# SBC_65C02_ISA_IRQ_v2.net
KiCad netlist of a schematic drawn in EAGLE
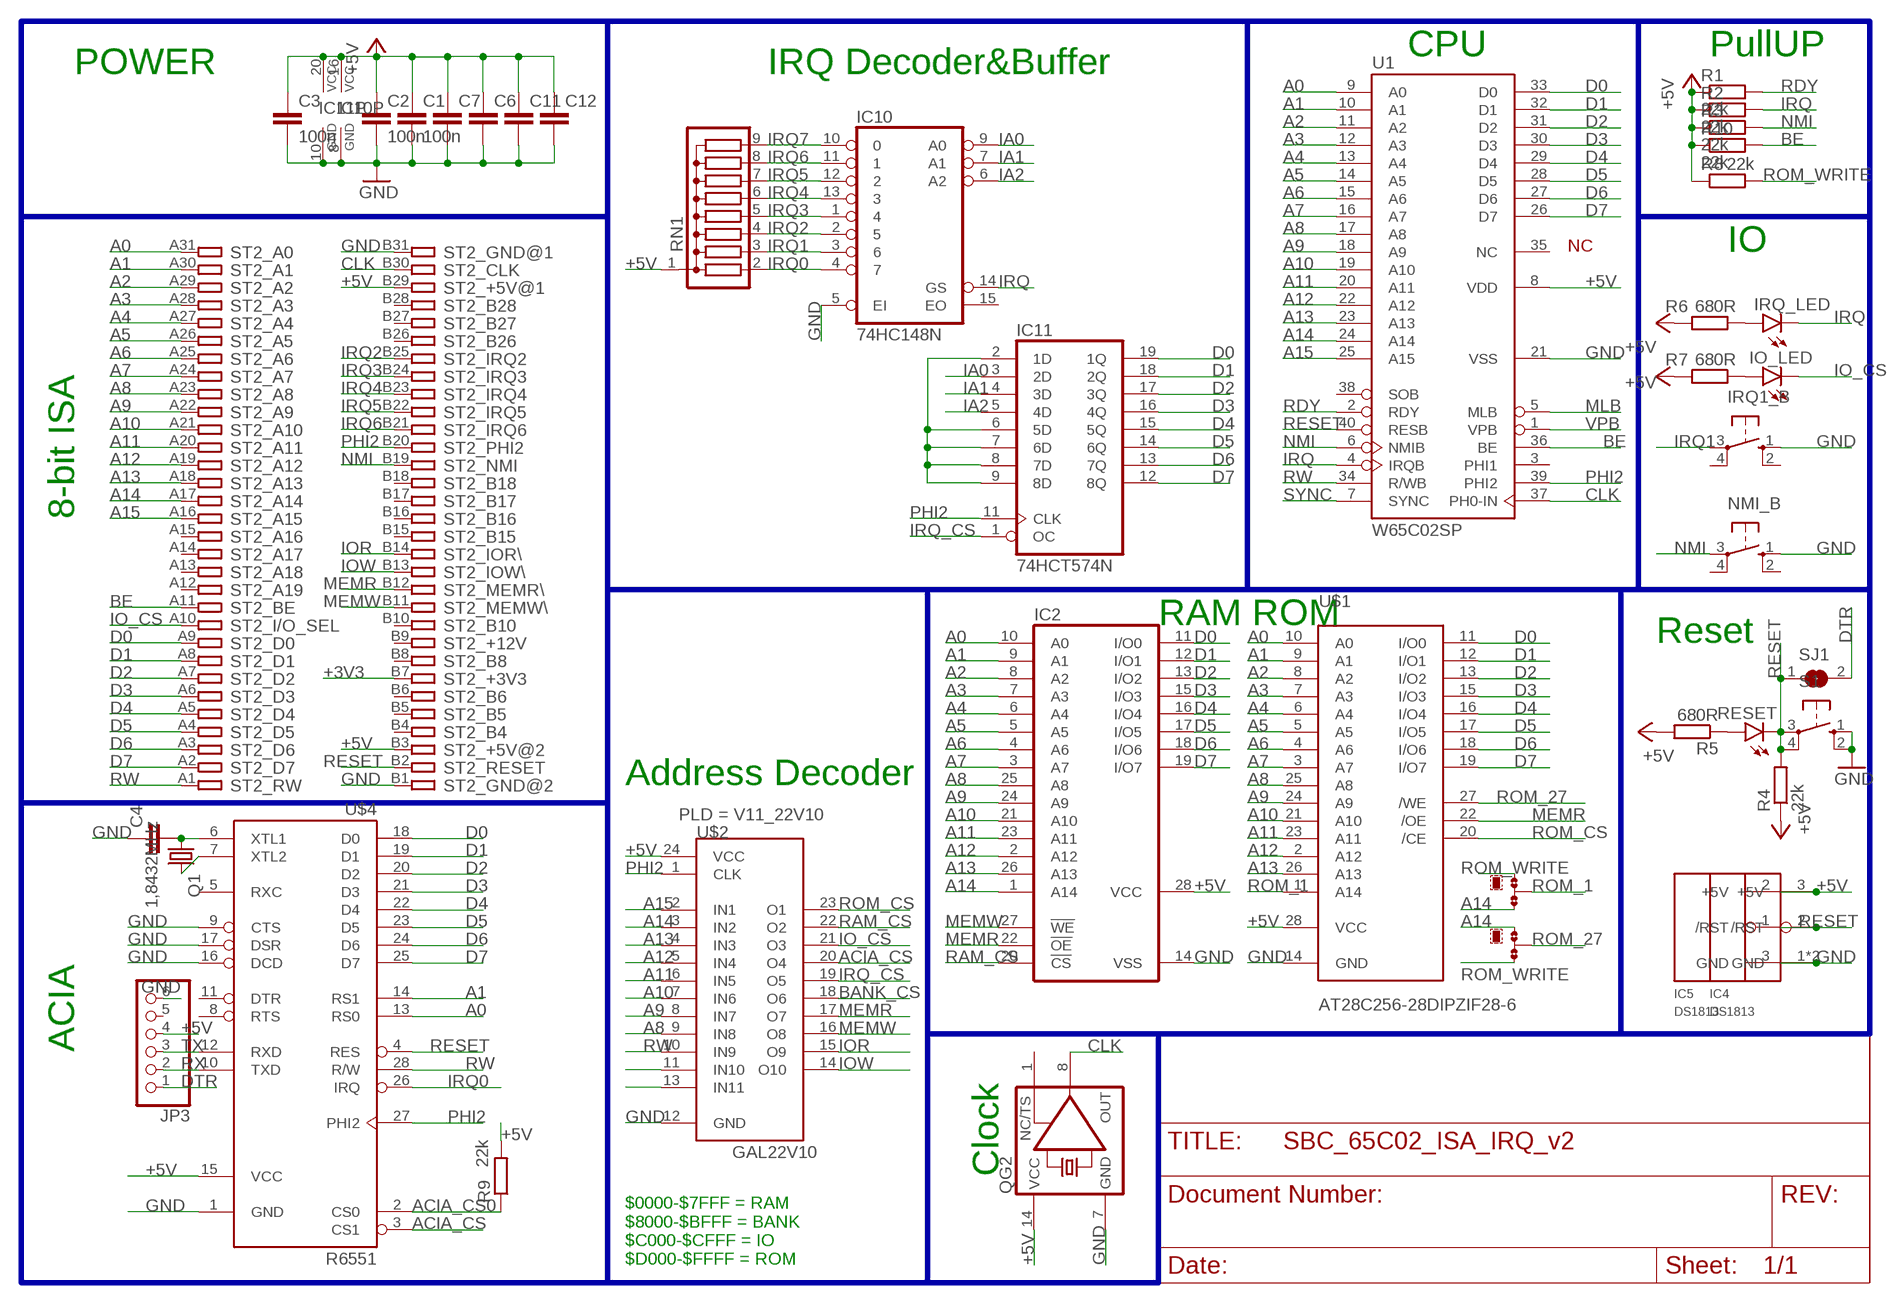
[diagram p0: schematic, sheet 1]

(export (version "E")
  (design (tool "Eeschema 10.0.6"))
  (components
    (comp (ref "C1")
      (value "100n")
      (footprint "eagle-import:C050-025X075")
      (libsource (lib "eagle-import") (part "C-EU050-025X075"))
    )
    (comp (ref "C2")
      (value "100n")
      (footprint "eagle-import:C050-025X075")
      (libsource (lib "eagle-import") (part "C-EU050-025X075"))
    )
    (comp (ref "C3")
      (value "100n")
      (footprint "eagle-import:C050-025X075")
      (libsource (lib "eagle-import") (part "C-EU050-025X075"))
    )
    (comp (ref "C4")
      (value "C-EU025-030X050")
      (footprint "eagle-import:C025-030X050")
      (libsource (lib "eagle-import") (part "rcl_334_C-EU025-030X050"))
    )
    (comp (ref "C6")
      (value "C-EU050-035X075")
      (footprint "eagle-import:C050-035X075")
      (libsource (lib "eagle-import") (part "rcl_334_C-EU050-035X075"))
    )
    (comp (ref "C7")
      (value "C-EU050-035X075")
      (footprint "eagle-import:C050-035X075")
      (libsource (lib "eagle-import") (part "rcl_334_C-EU050-035X075"))
    )
    (comp (ref "C11")
      (value "C-EU050-035X075")
      (footprint "eagle-import:C050-035X075")
      (libsource (lib "eagle-import") (part "rcl_334_C-EU050-035X075"))
    )
    (comp (ref "C12")
      (value "C-EU050-035X075")
      (footprint "eagle-import:C050-035X075")
      (libsource (lib "eagle-import") (part "rcl_334_C-EU050-035X075"))
    )
    (comp (ref "IC2")
      (value "62256P")
      (footprint "eagle-import:DIL28-6")
      (libsource (lib "eagle-import") (part "62256P"))
    )
    (comp (ref "IC4")
      (value "DS1813")
      (footprint "eagle-import:SOT223")
      (libsource (lib "eagle-import") (part "DS1813SOT-223"))
    )
    (comp (ref "IC5")
      (value "DS1813")
      (footprint "eagle-import:TO-92")
      (libsource (lib "eagle-import") (part "DS1813"))
    )
    (comp (ref "IC10")
      (value "74HC148N")
      (footprint "eagle-import:DIL16")
      (libsource (lib "eagle-import") (part "74148NHC"))
    )
    (comp (ref "IC11")
      (value "74HCT574N")
      (footprint "eagle-import:DIL20")
      (libsource (lib "eagle-import") (part "74574NHCT"))
    )
    (comp (ref "IO_LED")
      (value "LED5MM")
      (footprint "eagle-import:LED5MM")
      (libsource (lib "eagle-import") (part "LED5MM"))
    )
    (comp (ref "IRQ1_B")
      (value "10-XX")
      (footprint "eagle-import:B3F-10XX")
      (fields (field (name "MPN") "B3F-1000"))
      (libsource (lib "eagle-import") (part "10-XX"))
    )
    (comp (ref "IRQ_LED")
      (value "LED5MM")
      (footprint "eagle-import:LED5MM")
      (libsource (lib "eagle-import") (part "LED5MM"))
    )
    (comp (ref "JP3")
      (value "PINHD-1X6/90")
      (footprint "eagle-import:1X06_90")
      (libsource (lib "eagle-import") (part "PINHD-1X6/90"))
    )
    (comp (ref "NMI_B")
      (value "10-XX")
      (footprint "eagle-import:B3F-10XX")
      (fields (field (name "MPN") "B3F-1000"))
      (libsource (lib "eagle-import") (part "10-XX"))
    )
    (comp (ref "Q1")
      (value "1,8432MHz")
      (footprint "eagle-import:HC49_S")
      (libsource (lib "eagle-import") (part "CRYSTALHC49S"))
    )
    (comp (ref "QG2")
      (value "XO-14")
      (footprint "eagle-import:DIL14S")
      (libsource (lib "eagle-import") (part "XO-14"))
    )
    (comp (ref "R1")
      (value "22k")
      (footprint "eagle-import:0207_10")
      (libsource (lib "eagle-import") (part "R-EU_0207/10"))
    )
    (comp (ref "R2")
      (value "22k")
      (footprint "eagle-import:0207_10")
      (libsource (lib "eagle-import") (part "R-EU_0207/10"))
    )
    (comp (ref "R3")
      (value "22k")
      (footprint "eagle-import:0207_10")
      (libsource (lib "eagle-import") (part "R-EU_0207/10"))
    )
    (comp (ref "R4")
      (value "22k")
      (footprint "eagle-import:0207_10")
      (libsource (lib "eagle-import") (part "resistor_348_R-EU_0207/10"))
    )
    (comp (ref "R5")
      (value "680R")
      (footprint "eagle-import:0207_10")
      (libsource (lib "eagle-import") (part "resistor_348_R-EU_0207/10"))
    )
    (comp (ref "R6")
      (value "680R")
      (footprint "eagle-import:0207_10")
      (libsource (lib "eagle-import") (part "resistor_348_R-EU_0207/10"))
    )
    (comp (ref "R7")
      (value "680R")
      (footprint "eagle-import:0207_10")
      (libsource (lib "eagle-import") (part "resistor_348_R-EU_0207/10"))
    )
    (comp (ref "R8")
      (value "22k")
      (footprint "eagle-import:0207_10")
      (libsource (lib "eagle-import") (part "rcl_334_R-EU_0207/10"))
    )
    (comp (ref "R9")
      (value "22k")
      (footprint "eagle-import:0207_10")
      (libsource (lib "eagle-import") (part "rcl_334_R-EU_0207/10"))
    )
    (comp (ref "R10")
      (value "22k")
      (footprint "eagle-import:0207_10")
      (libsource (lib "eagle-import") (part "R-EU_0207/10"))
    )
    (comp (ref "RESET")
      (value "LED5MM")
      (footprint "eagle-import:LED5MM")
      (libsource (lib "eagle-import") (part "LED5MM"))
    )
    (comp (ref "RN1")
      (value "G08R")
      (footprint "eagle-import:SIL9")
      (libsource (lib "eagle-import") (part "G08R"))
    )
    (comp (ref "ROM_1")
      (value "0R-JUMPA")
      (footprint "eagle-import:A0R-JMP")
      (libsource (lib "eagle-import") (part "0R-JUMPA"))
    )
    (comp (ref "ROM_27")
      (value "0R-JUMPA")
      (footprint "eagle-import:A0R-JMP")
      (libsource (lib "eagle-import") (part "0R-JUMPA"))
    )
    (comp (ref "S1")
      (value "10-XX")
      (footprint "eagle-import:B3F-10XX")
      (fields (field (name "MPN") "B3F-1000"))
      (libsource (lib "eagle-import") (part "10-XX"))
    )
    (comp (ref "SJ1") (value "SJ") (footprint "eagle-import:SJ") (libsource (lib "eagle-import") (part "SJ")))
    (comp (ref "ST2")
      (value "IBM8BIT_ISA")
      (footprint "eagle-import:IBM8BIT")
      (libsource (lib "eagle-import") (part "IBM8BIT_ISA"))
    )
    (comp (ref "U$1")
      (value "AT28C256-28DIPZIF28-6")
      (footprint "eagle-import:228-1277-00-0602J")
      (libsource (lib "eagle-import") (part "AT28C256-28DIPZIF28-6"))
    )
    (comp (ref "U$2")
      (value "GAL22V10")
      (footprint "eagle-import:DIL28_1")
      (libsource (lib "eagle-import") (part "GAL22V10"))
    )
    (comp (ref "U$4")
      (value "R6551")
      (footprint "eagle-import:DIP-28")
      (libsource (lib "eagle-import") (part "R6551"))
    )
    (comp (ref "U1")
      (value "W65C02SP")
      (footprint "eagle-import:DIP-40")
      (libsource (lib "eagle-import") (part "W65C02SP"))
    )
  )
  (nets
    (net (code "1") (name "+5V") (class "Default")
      (node (ref "C1") (pin "1") (pinfunction "1_1") (pintype "passive"))
      (node (ref "C11") (pin "1") (pinfunction "1_1") (pintype "passive"))
      (node (ref "C12") (pin "1") (pinfunction "1_1") (pintype "passive"))
      (node (ref "C2") (pin "1") (pinfunction "1_1") (pintype "passive"))
      (node (ref "C3") (pin "1") (pinfunction "1_1") (pintype "passive"))
      (node (ref "C6") (pin "1") (pinfunction "1_1") (pintype "passive"))
      (node (ref "C7") (pin "1") (pinfunction "1_1") (pintype "passive"))
      (node (ref "IC10") (pin "16") (pinfunction "VCC_16") (pintype "power_in"))
      (node (ref "IC11") (pin "20") (pinfunction "VCC_20") (pintype "power_in"))
      (node (ref "IC2") (pin "28") (pinfunction "VCC_28") (pintype "power_in"))
      (node (ref "IC4") (pin "3") (pinfunction "+5V_3") (pintype "power_in"))
      (node (ref "IC5") (pin "2") (pinfunction "+5V_2") (pintype "power_in"))
      (node (ref "JP3") (pin "4") (pinfunction "4_4") (pintype "passive"))
      (node (ref "QG2") (pin "14") (pinfunction "VCC_14") (pintype "power_in"))
      (node (ref "R1") (pin "1") (pinfunction "1_1") (pintype "passive"))
      (node (ref "R10") (pin "1") (pinfunction "1_1") (pintype "passive"))
      (node (ref "R2") (pin "1") (pinfunction "1_1") (pintype "passive"))
      (node (ref "R3") (pin "1") (pinfunction "1_1") (pintype "passive"))
      (node (ref "R4") (pin "1") (pinfunction "1_1") (pintype "passive"))
      (node (ref "R5") (pin "2") (pinfunction "2_2") (pintype "passive"))
      (node (ref "R6") (pin "2") (pinfunction "2_2") (pintype "passive"))
      (node (ref "R7") (pin "2") (pinfunction "2_2") (pintype "passive"))
      (node (ref "R8") (pin "1") (pinfunction "1_1") (pintype "passive"))
      (node (ref "R9") (pin "2") (pinfunction "2_2") (pintype "passive"))
      (node (ref "RN1") (pin "1") (pinfunction "1_1") (pintype "passive"))
      (node (ref "ST2") (pin "B29") (pinfunction "P_B29") (pintype "bidirectional"))
      (node (ref "ST2") (pin "B3") (pinfunction "P_B3") (pintype "bidirectional"))
      (node (ref "U$1") (pin "28") (pinfunction "VCC_28") (pintype "bidirectional"))
      (node (ref "U$2") (pin "24") (pinfunction "VCC_24") (pintype "bidirectional"))
      (node (ref "U$4") (pin "15") (pinfunction "VCC_15") (pintype "power_in"))
      (node (ref "U1") (pin "8") (pinfunction "VDD_8") (pintype "power_in"))
    )
    (net (code "2") (name "/+3V3") (class "Default")
      (node (ref "ST2") (pin "B7") (pinfunction "P_B7") (pintype "bidirectional"))
    )
    (net (code "3") (name "/A0") (class "Default")
      (node (ref "IC2") (pin "10") (pinfunction "A0_10") (pintype "input"))
      (node (ref "ST2") (pin "A31") (pinfunction "P_A31") (pintype "bidirectional"))
      (node (ref "U$1") (pin "10") (pinfunction "A0_10") (pintype "bidirectional"))
      (node (ref "U$4") (pin "13") (pinfunction "RS0_13") (pintype "input"))
      (node (ref "U1") (pin "9") (pinfunction "A0_9") (pintype "bidirectional"))
    )
    (net (code "4") (name "/A1") (class "Default")
      (node (ref "IC2") (pin "9") (pinfunction "A1_9") (pintype "input"))
      (node (ref "ST2") (pin "A30") (pinfunction "P_A30") (pintype "bidirectional"))
      (node (ref "U$1") (pin "9") (pinfunction "A1_9") (pintype "bidirectional"))
      (node (ref "U$4") (pin "14") (pinfunction "RS1_14") (pintype "input"))
      (node (ref "U1") (pin "10") (pinfunction "A1_10") (pintype "bidirectional"))
    )
    (net (code "5") (name "/A2") (class "Default")
      (node (ref "IC2") (pin "8") (pinfunction "A2_8") (pintype "input"))
      (node (ref "ST2") (pin "A29") (pinfunction "P_A29") (pintype "bidirectional"))
      (node (ref "U$1") (pin "8") (pinfunction "A2_8") (pintype "bidirectional"))
      (node (ref "U1") (pin "11") (pinfunction "A2_11") (pintype "bidirectional"))
    )
    (net (code "6") (name "/A3") (class "Default")
      (node (ref "IC2") (pin "7") (pinfunction "A3_7") (pintype "input"))
      (node (ref "ST2") (pin "A28") (pinfunction "P_A28") (pintype "bidirectional"))
      (node (ref "U$1") (pin "7") (pinfunction "A3_7") (pintype "bidirectional"))
      (node (ref "U1") (pin "12") (pinfunction "A3_12") (pintype "bidirectional"))
    )
    (net (code "7") (name "/A4") (class "Default")
      (node (ref "IC2") (pin "6") (pinfunction "A4_6") (pintype "input"))
      (node (ref "ST2") (pin "A27") (pinfunction "P_A27") (pintype "bidirectional"))
      (node (ref "U$1") (pin "6") (pinfunction "A4_6") (pintype "bidirectional"))
      (node (ref "U1") (pin "13") (pinfunction "A4_13") (pintype "bidirectional"))
    )
    (net (code "8") (name "/A5") (class "Default")
      (node (ref "IC2") (pin "5") (pinfunction "A5_5") (pintype "input"))
      (node (ref "ST2") (pin "A26") (pinfunction "P_A26") (pintype "bidirectional"))
      (node (ref "U$1") (pin "5") (pinfunction "A5_5") (pintype "bidirectional"))
      (node (ref "U1") (pin "14") (pinfunction "A5_14") (pintype "bidirectional"))
    )
    (net (code "9") (name "/A6") (class "Default")
      (node (ref "IC2") (pin "4") (pinfunction "A6_4") (pintype "input"))
      (node (ref "ST2") (pin "A25") (pinfunction "P_A25") (pintype "bidirectional"))
      (node (ref "U$1") (pin "4") (pinfunction "A6_4") (pintype "bidirectional"))
      (node (ref "U1") (pin "15") (pinfunction "A6_15") (pintype "bidirectional"))
    )
    (net (code "10") (name "/A7") (class "Default")
      (node (ref "IC2") (pin "3") (pinfunction "A7_3") (pintype "input"))
      (node (ref "ST2") (pin "A24") (pinfunction "P_A24") (pintype "bidirectional"))
      (node (ref "U$1") (pin "3") (pinfunction "A7_3") (pintype "bidirectional"))
      (node (ref "U1") (pin "16") (pinfunction "A7_16") (pintype "bidirectional"))
    )
    (net (code "11") (name "/A8") (class "Default")
      (node (ref "IC2") (pin "25") (pinfunction "A8_25") (pintype "input"))
      (node (ref "ST2") (pin "A23") (pinfunction "P_A23") (pintype "bidirectional"))
      (node (ref "U$1") (pin "25") (pinfunction "A8_25") (pintype "bidirectional"))
      (node (ref "U$2") (pin "9") (pinfunction "IN8_9") (pintype "bidirectional"))
      (node (ref "U1") (pin "17") (pinfunction "A8_17") (pintype "bidirectional"))
    )
    (net (code "12") (name "/A9") (class "Default")
      (node (ref "IC2") (pin "24") (pinfunction "A9_24") (pintype "input"))
      (node (ref "ST2") (pin "A22") (pinfunction "P_A22") (pintype "bidirectional"))
      (node (ref "U$1") (pin "24") (pinfunction "A9_24") (pintype "bidirectional"))
      (node (ref "U$2") (pin "8") (pinfunction "IN7_8") (pintype "bidirectional"))
      (node (ref "U1") (pin "18") (pinfunction "A9_18") (pintype "bidirectional"))
    )
    (net (code "13") (name "/A10") (class "Default")
      (node (ref "IC2") (pin "21") (pinfunction "A10_21") (pintype "input"))
      (node (ref "ST2") (pin "A21") (pinfunction "P_A21") (pintype "bidirectional"))
      (node (ref "U$1") (pin "21") (pinfunction "A10_21") (pintype "bidirectional"))
      (node (ref "U$2") (pin "7") (pinfunction "IN6_7") (pintype "bidirectional"))
      (node (ref "U1") (pin "19") (pinfunction "A10_19") (pintype "bidirectional"))
    )
    (net (code "14") (name "/A11") (class "Default")
      (node (ref "IC2") (pin "23") (pinfunction "A11_23") (pintype "input"))
      (node (ref "ST2") (pin "A20") (pinfunction "P_A20") (pintype "bidirectional"))
      (node (ref "U$1") (pin "23") (pinfunction "A11_23") (pintype "bidirectional"))
      (node (ref "U$2") (pin "6") (pinfunction "IN5_6") (pintype "bidirectional"))
      (node (ref "U1") (pin "20") (pinfunction "A11_20") (pintype "bidirectional"))
    )
    (net (code "15") (name "/A12") (class "Default")
      (node (ref "IC2") (pin "2") (pinfunction "A12_2") (pintype "input"))
      (node (ref "ST2") (pin "A19") (pinfunction "P_A19") (pintype "bidirectional"))
      (node (ref "U$1") (pin "2") (pinfunction "A12_2") (pintype "bidirectional"))
      (node (ref "U$2") (pin "5") (pinfunction "IN4_5") (pintype "bidirectional"))
      (node (ref "U1") (pin "22") (pinfunction "A12_22") (pintype "bidirectional"))
    )
    (net (code "16") (name "/A13") (class "Default")
      (node (ref "IC2") (pin "26") (pinfunction "A13_26") (pintype "input"))
      (node (ref "ST2") (pin "A18") (pinfunction "P_A18") (pintype "bidirectional"))
      (node (ref "U$1") (pin "26") (pinfunction "A13_26") (pintype "bidirectional"))
      (node (ref "U$2") (pin "4") (pinfunction "IN3_4") (pintype "bidirectional"))
      (node (ref "U1") (pin "23") (pinfunction "A13_23") (pintype "bidirectional"))
    )
    (net (code "17") (name "/A14") (class "Default")
      (node (ref "IC2") (pin "1") (pinfunction "A14_1") (pintype "input"))
      (node (ref "ROM_1") (pin "3") (pinfunction "3_3") (pintype "passive"))
      (node (ref "ROM_27") (pin "1") (pinfunction "1_1") (pintype "passive"))
      (node (ref "ST2") (pin "A17") (pinfunction "P_A17") (pintype "bidirectional"))
      (node (ref "U$2") (pin "3") (pinfunction "IN2_3") (pintype "bidirectional"))
      (node (ref "U1") (pin "24") (pinfunction "A14_24") (pintype "bidirectional"))
    )
    (net (code "18") (name "/A15") (class "Default")
      (node (ref "ST2") (pin "A16") (pinfunction "P_A16") (pintype "bidirectional"))
      (node (ref "U$2") (pin "2") (pinfunction "IN1_2") (pintype "bidirectional"))
      (node (ref "U1") (pin "25") (pinfunction "A15_25") (pintype "bidirectional"))
    )
    (net (code "19") (name "/ACIA_CS") (class "Default")
      (node (ref "U$2") (pin "20") (pinfunction "O4_20") (pintype "bidirectional"))
      (node (ref "U$4") (pin "3") (pinfunction "CS1_3") (pintype "input"))
    )
    (net (code "20") (name "/ACIA_CS0") (class "Default")
      (node (ref "R9") (pin "1") (pinfunction "1_1") (pintype "passive"))
      (node (ref "U$4") (pin "2") (pinfunction "CS0_2") (pintype "input"))
    )
    (net (code "21") (name "/BANK_CS") (class "Default")
      (node (ref "U$2") (pin "18") (pinfunction "O6_18") (pintype "bidirectional"))
    )
    (net (code "22") (name "/BE") (class "Default")
      (node (ref "R10") (pin "2") (pinfunction "2_2") (pintype "passive"))
      (node (ref "ST2") (pin "A11") (pinfunction "P_A11") (pintype "bidirectional"))
      (node (ref "U1") (pin "36") (pinfunction "BE_36") (pintype "input"))
    )
    (net (code "23") (name "/CLK") (class "Default")
      (node (ref "QG2") (pin "8") (pinfunction "OUT_8") (pintype "output"))
      (node (ref "ST2") (pin "B30") (pinfunction "P_B30") (pintype "bidirectional"))
      (node (ref "U1") (pin "37") (pinfunction "PH0-IN_37") (pintype "input"))
    )
    (net (code "24") (name "/D0") (class "Default")
      (node (ref "IC11") (pin "19") (pinfunction "1Q_19") (pintype "tri_state"))
      (node (ref "IC2") (pin "11") (pinfunction "I/O0_11") (pintype "bidirectional"))
      (node (ref "ST2") (pin "A9") (pinfunction "P_A9") (pintype "bidirectional"))
      (node (ref "U$1") (pin "11") (pinfunction "I/O0_11") (pintype "bidirectional"))
      (node (ref "U$4") (pin "18") (pinfunction "D0_18") (pintype "bidirectional"))
      (node (ref "U1") (pin "33") (pinfunction "D0_33") (pintype "bidirectional"))
    )
    (net (code "25") (name "/D1") (class "Default")
      (node (ref "IC11") (pin "18") (pinfunction "2Q_18") (pintype "tri_state"))
      (node (ref "IC2") (pin "12") (pinfunction "I/O1_12") (pintype "bidirectional"))
      (node (ref "ST2") (pin "A8") (pinfunction "P_A8") (pintype "bidirectional"))
      (node (ref "U$1") (pin "12") (pinfunction "I/O1_12") (pintype "bidirectional"))
      (node (ref "U$4") (pin "19") (pinfunction "D1_19") (pintype "bidirectional"))
      (node (ref "U1") (pin "32") (pinfunction "D1_32") (pintype "bidirectional"))
    )
    (net (code "26") (name "/D2") (class "Default")
      (node (ref "IC11") (pin "17") (pinfunction "3Q_17") (pintype "tri_state"))
      (node (ref "IC2") (pin "13") (pinfunction "I/O2_13") (pintype "bidirectional"))
      (node (ref "ST2") (pin "A7") (pinfunction "P_A7") (pintype "bidirectional"))
      (node (ref "U$1") (pin "13") (pinfunction "I/O2_13") (pintype "bidirectional"))
      (node (ref "U$4") (pin "20") (pinfunction "D2_20") (pintype "bidirectional"))
      (node (ref "U1") (pin "31") (pinfunction "D2_31") (pintype "bidirectional"))
    )
    (net (code "27") (name "/D3") (class "Default")
      (node (ref "IC11") (pin "16") (pinfunction "4Q_16") (pintype "tri_state"))
      (node (ref "IC2") (pin "15") (pinfunction "I/O3_15") (pintype "bidirectional"))
      (node (ref "ST2") (pin "A6") (pinfunction "P_A6") (pintype "bidirectional"))
      (node (ref "U$1") (pin "15") (pinfunction "I/O3_15") (pintype "bidirectional"))
      (node (ref "U$4") (pin "21") (pinfunction "D3_21") (pintype "bidirectional"))
      (node (ref "U1") (pin "30") (pinfunction "D3_30") (pintype "bidirectional"))
    )
    (net (code "28") (name "/D4") (class "Default")
      (node (ref "IC11") (pin "15") (pinfunction "5Q_15") (pintype "tri_state"))
      (node (ref "IC2") (pin "16") (pinfunction "I/O4_16") (pintype "bidirectional"))
      (node (ref "ST2") (pin "A5") (pinfunction "P_A5") (pintype "bidirectional"))
      (node (ref "U$1") (pin "16") (pinfunction "I/O4_16") (pintype "bidirectional"))
      (node (ref "U$4") (pin "22") (pinfunction "D4_22") (pintype "bidirectional"))
      (node (ref "U1") (pin "29") (pinfunction "D4_29") (pintype "bidirectional"))
    )
    (net (code "29") (name "/D5") (class "Default")
      (node (ref "IC11") (pin "14") (pinfunction "6Q_14") (pintype "tri_state"))
      (node (ref "IC2") (pin "17") (pinfunction "I/O5_17") (pintype "bidirectional"))
      (node (ref "ST2") (pin "A4") (pinfunction "P_A4") (pintype "bidirectional"))
      (node (ref "U$1") (pin "17") (pinfunction "I/O5_17") (pintype "bidirectional"))
      (node (ref "U$4") (pin "23") (pinfunction "D5_23") (pintype "bidirectional"))
      (node (ref "U1") (pin "28") (pinfunction "D5_28") (pintype "bidirectional"))
    )
    (net (code "30") (name "/D6") (class "Default")
      (node (ref "IC11") (pin "13") (pinfunction "7Q_13") (pintype "tri_state"))
      (node (ref "IC2") (pin "18") (pinfunction "I/O6_18") (pintype "bidirectional"))
      (node (ref "ST2") (pin "A3") (pinfunction "P_A3") (pintype "bidirectional"))
      (node (ref "U$1") (pin "18") (pinfunction "I/O6_18") (pintype "bidirectional"))
      (node (ref "U$4") (pin "24") (pinfunction "D6_24") (pintype "bidirectional"))
      (node (ref "U1") (pin "27") (pinfunction "D6_27") (pintype "bidirectional"))
    )
    (net (code "31") (name "/D7") (class "Default")
      (node (ref "IC11") (pin "12") (pinfunction "8Q_12") (pintype "tri_state"))
      (node (ref "IC2") (pin "19") (pinfunction "I/O7_19") (pintype "bidirectional"))
      (node (ref "ST2") (pin "A2") (pinfunction "P_A2") (pintype "bidirectional"))
      (node (ref "U$1") (pin "19") (pinfunction "I/O7_19") (pintype "bidirectional"))
      (node (ref "U$4") (pin "25") (pinfunction "D7_25") (pintype "bidirectional"))
      (node (ref "U1") (pin "26") (pinfunction "D7_26") (pintype "bidirectional"))
    )
    (net (code "32") (name "/DTR") (class "Default")
      (node (ref "JP3") (pin "1") (pinfunction "1_1") (pintype "passive"))
      (node (ref "SJ1") (pin "2") (pinfunction "2_2") (pintype "passive"))
    )
    (net (code "33") (name "/IA0") (class "Default")
      (node (ref "IC10") (pin "9") (pinfunction "A0_9") (pintype "output"))
      (node (ref "IC11") (pin "3") (pinfunction "2D_3") (pintype "input"))
    )
    (net (code "34") (name "/IA1") (class "Default")
      (node (ref "IC10") (pin "7") (pinfunction "A1_7") (pintype "output"))
      (node (ref "IC11") (pin "4") (pinfunction "3D_4") (pintype "input"))
    )
    (net (code "35") (name "/IA2") (class "Default")
      (node (ref "IC10") (pin "6") (pinfunction "A2_6") (pintype "output"))
      (node (ref "IC11") (pin "5") (pinfunction "4D_5") (pintype "input"))
    )
    (net (code "36") (name "/IOR") (class "Default")
      (node (ref "ST2") (pin "B14") (pinfunction "P_B14") (pintype "bidirectional"))
      (node (ref "U$2") (pin "15") (pinfunction "O9_15") (pintype "bidirectional"))
    )
    (net (code "37") (name "/IOW") (class "Default")
      (node (ref "ST2") (pin "B13") (pinfunction "P_B13") (pintype "bidirectional"))
      (node (ref "U$2") (pin "14") (pinfunction "O10_14") (pintype "bidirectional"))
    )
    (net (code "38") (name "/IO_CS") (class "Default")
      (node (ref "IO_LED") (pin "K") (pinfunction "C_K") (pintype "passive"))
      (node (ref "ST2") (pin "A10") (pinfunction "P_A10") (pintype "bidirectional"))
      (node (ref "U$2") (pin "21") (pinfunction "O3_21") (pintype "bidirectional"))
    )
    (net (code "39") (name "/IRQ") (class "Default")
      (node (ref "IC10") (pin "14") (pinfunction "GS_14") (pintype "output"))
      (node (ref "IRQ_LED") (pin "K") (pinfunction "C_K") (pintype "passive"))
      (node (ref "R2") (pin "2") (pinfunction "2_2") (pintype "passive"))
      (node (ref "U1") (pin "4") (pinfunction "IRQB_4") (pintype "input"))
    )
    (net (code "40") (name "/IRQ0") (class "Default")
      (node (ref "IC10") (pin "4") (pinfunction "7_4") (pintype "input"))
      (node (ref "RN1") (pin "2") (pinfunction "2_2") (pintype "passive"))
      (node (ref "U$4") (pin "26") (pinfunction "IRQ_26") (pintype "output"))
    )
    (net (code "41") (name "/IRQ1") (class "Default")
      (node (ref "IC10") (pin "3") (pinfunction "6_3") (pintype "input"))
      (node (ref "IRQ1_B") (pin "3") (pinfunction "P_3") (pintype "passive"))
      (node (ref "RN1") (pin "3") (pinfunction "3_3") (pintype "passive"))
    )
    (net (code "42") (name "/IRQ2") (class "Default")
      (node (ref "IC10") (pin "2") (pinfunction "5_2") (pintype "input"))
      (node (ref "RN1") (pin "4") (pinfunction "4_4") (pintype "passive"))
      (node (ref "ST2") (pin "B25") (pinfunction "P_B25") (pintype "bidirectional"))
    )
    (net (code "43") (name "/IRQ3") (class "Default")
      (node (ref "IC10") (pin "1") (pinfunction "4_1") (pintype "input"))
      (node (ref "RN1") (pin "5") (pinfunction "5_5") (pintype "passive"))
      (node (ref "ST2") (pin "B24") (pinfunction "P_B24") (pintype "bidirectional"))
    )
    (net (code "44") (name "/IRQ4") (class "Default")
      (node (ref "IC10") (pin "13") (pinfunction "3_13") (pintype "input"))
      (node (ref "RN1") (pin "6") (pinfunction "6_6") (pintype "passive"))
      (node (ref "ST2") (pin "B23") (pinfunction "P_B23") (pintype "bidirectional"))
    )
    (net (code "45") (name "/IRQ5") (class "Default")
      (node (ref "IC10") (pin "12") (pinfunction "2_12") (pintype "input"))
      (node (ref "RN1") (pin "7") (pinfunction "7_7") (pintype "passive"))
      (node (ref "ST2") (pin "B22") (pinfunction "P_B22") (pintype "bidirectional"))
    )
    (net (code "46") (name "/IRQ6") (class "Default")
      (node (ref "IC10") (pin "11") (pinfunction "1_11") (pintype "input"))
      (node (ref "RN1") (pin "8") (pinfunction "8_8") (pintype "passive"))
      (node (ref "ST2") (pin "B21") (pinfunction "P_B21") (pintype "bidirectional"))
    )
    (net (code "47") (name "/IRQ7") (class "Default")
      (node (ref "IC10") (pin "10") (pinfunction "0_10") (pintype "input"))
      (node (ref "RN1") (pin "9") (pinfunction "9_9") (pintype "passive"))
    )
    (net (code "48") (name "/IRQ_CS") (class "Default")
      (node (ref "IC11") (pin "1") (pinfunction "OC_1") (pintype "input"))
      (node (ref "U$2") (pin "19") (pinfunction "O5_19") (pintype "bidirectional"))
    )
    (net (code "49") (name "/MEMR") (class "Default")
      (node (ref "IC2") (pin "22") (pinfunction "~{OE}_22") (pintype "input"))
      (node (ref "ST2") (pin "B12") (pinfunction "P_B12") (pintype "bidirectional"))
      (node (ref "U$1") (pin "22") (pinfunction "/OE_22") (pintype "bidirectional"))
      (node (ref "U$2") (pin "17") (pinfunction "O7_17") (pintype "bidirectional"))
    )
    (net (code "50") (name "/MEMW") (class "Default")
      (node (ref "IC2") (pin "27") (pinfunction "~{WE}_27") (pintype "input"))
      (node (ref "ST2") (pin "B11") (pinfunction "P_B11") (pintype "bidirectional"))
      (node (ref "U$2") (pin "16") (pinfunction "O8_16") (pintype "bidirectional"))
    )
    (net (code "51") (name "/MLB") (class "Default")
      (node (ref "U1") (pin "5") (pinfunction "MLB_5") (pintype "output"))
    )
    (net (code "52") (name "/NMI") (class "Default")
      (node (ref "NMI_B") (pin "3") (pinfunction "P_3") (pintype "passive"))
      (node (ref "R3") (pin "2") (pinfunction "2_2") (pintype "passive"))
      (node (ref "ST2") (pin "B19") (pinfunction "P_B19") (pintype "bidirectional"))
      (node (ref "U1") (pin "6") (pinfunction "NMIB_6") (pintype "input"))
    )
    (net (code "53") (name "/PHI2") (class "Default")
      (node (ref "IC11") (pin "11") (pinfunction "CLK_11") (pintype "input"))
      (node (ref "ST2") (pin "B20") (pinfunction "P_B20") (pintype "bidirectional"))
      (node (ref "U$2") (pin "1") (pinfunction "CLK_1") (pintype "bidirectional"))
      (node (ref "U$4") (pin "27") (pinfunction "PHI2_27") (pintype "input"))
      (node (ref "U1") (pin "39") (pinfunction "PHI2_39") (pintype "output"))
    )
    (net (code "54") (name "/RAM_CS") (class "Default")
      (node (ref "IC2") (pin "20") (pinfunction "~{CS}_20") (pintype "input"))
      (node (ref "U$2") (pin "22") (pinfunction "O2_22") (pintype "bidirectional"))
    )
    (net (code "55") (name "/RDY") (class "Default")
      (node (ref "R1") (pin "2") (pinfunction "2_2") (pintype "passive"))
      (node (ref "U1") (pin "2") (pinfunction "RDY_2") (pintype "bidirectional"))
    )
    (net (code "56") (name "/RESET") (class "Default")
      (node (ref "IC4") (pin "2") (pinfunction "/RST_2") (pintype "passive"))
      (node (ref "IC5") (pin "1") (pinfunction "/RST_1") (pintype "passive"))
      (node (ref "R4") (pin "2") (pinfunction "2_2") (pintype "passive"))
      (node (ref "RESET") (pin "K") (pinfunction "C_K") (pintype "passive"))
      (node (ref "S1") (pin "3") (pinfunction "P_3") (pintype "passive"))
      (node (ref "S1") (pin "4") (pinfunction "P1_4") (pintype "passive"))
      (node (ref "SJ1") (pin "1") (pinfunction "1_1") (pintype "passive"))
      (node (ref "ST2") (pin "B2") (pinfunction "P_B2") (pintype "bidirectional"))
      (node (ref "U$4") (pin "4") (pinfunction "RES_4") (pintype "input"))
      (node (ref "U1") (pin "40") (pinfunction "RESB_40") (pintype "input"))
    )
    (net (code "57") (name "/ROM_1") (class "Default")
      (node (ref "ROM_1") (pin "2") (pinfunction "2_2") (pintype "passive"))
      (node (ref "U$1") (pin "1") (pinfunction "A14_1") (pintype "bidirectional"))
    )
    (net (code "58") (name "/ROM_27") (class "Default")
      (node (ref "ROM_27") (pin "2") (pinfunction "2_2") (pintype "passive"))
      (node (ref "U$1") (pin "27") (pinfunction "/WE_27") (pintype "bidirectional"))
    )
    (net (code "59") (name "/ROM_CS") (class "Default")
      (node (ref "U$1") (pin "20") (pinfunction "/CE_20") (pintype "bidirectional"))
      (node (ref "U$2") (pin "23") (pinfunction "O1_23") (pintype "bidirectional"))
    )
    (net (code "60") (name "/ROM_WRITE") (class "Default")
      (node (ref "R8") (pin "2") (pinfunction "2_2") (pintype "passive"))
      (node (ref "ROM_1") (pin "1") (pinfunction "1_1") (pintype "passive"))
      (node (ref "ROM_27") (pin "3") (pinfunction "3_3") (pintype "passive"))
    )
    (net (code "61") (name "/RW") (class "Default")
      (node (ref "ST2") (pin "A1") (pinfunction "P_A1") (pintype "bidirectional"))
      (node (ref "U$2") (pin "10") (pinfunction "IN9_10") (pintype "bidirectional"))
      (node (ref "U$4") (pin "28") (pinfunction "R/W_28") (pintype "input"))
      (node (ref "U1") (pin "34") (pinfunction "R/WB_34") (pintype "output"))
    )
    (net (code "62") (name "/RX") (class "Default")
      (node (ref "JP3") (pin "2") (pinfunction "2_2") (pintype "passive"))
      (node (ref "U$4") (pin "10") (pinfunction "TXD_10") (pintype "output"))
    )
    (net (code "63") (name "/SYNC") (class "Default")
      (node (ref "U1") (pin "7") (pinfunction "SYNC_7") (pintype "output"))
    )
    (net (code "64") (name "/TX") (class "Default")
      (node (ref "JP3") (pin "3") (pinfunction "3_3") (pintype "passive"))
      (node (ref "U$4") (pin "12") (pinfunction "RXD_12") (pintype "input"))
    )
    (net (code "65") (name "/VPB") (class "Default")
      (node (ref "U1") (pin "1") (pinfunction "VPB_1") (pintype "output"))
    )
    (net (code "66") (name "GND") (class "Default")
      (node (ref "C1") (pin "2") (pinfunction "2_2") (pintype "passive"))
      (node (ref "C11") (pin "2") (pinfunction "2_2") (pintype "passive"))
      (node (ref "C12") (pin "2") (pinfunction "2_2") (pintype "passive"))
      (node (ref "C2") (pin "2") (pinfunction "2_2") (pintype "passive"))
      (node (ref "C3") (pin "2") (pinfunction "2_2") (pintype "passive"))
      (node (ref "C4") (pin "1") (pinfunction "1_1") (pintype "passive"))
      (node (ref "C6") (pin "2") (pinfunction "2_2") (pintype "passive"))
      (node (ref "C7") (pin "2") (pinfunction "2_2") (pintype "passive"))
      (node (ref "IC10") (pin "5") (pinfunction "EI_5") (pintype "input"))
      (node (ref "IC10") (pin "8") (pinfunction "GND_8") (pintype "power_in"))
      (node (ref "IC11") (pin "10") (pinfunction "GND_10") (pintype "power_in"))
      (node (ref "IC2") (pin "14") (pinfunction "VSS_14") (pintype "power_in"))
      (node (ref "IC4") (pin "1") (pinfunction "GND_1") (pintype "power_in"))
      (node (ref "IC4") (pin "4") (pinfunction "GND_4") (pintype "power_in"))
      (node (ref "IC5") (pin "3") (pinfunction "GND_3") (pintype "power_in"))
      (node (ref "IRQ1_B") (pin "1") (pinfunction "S_1") (pintype "passive"))
      (node (ref "JP3") (pin "6") (pinfunction "6_6") (pintype "passive"))
      (node (ref "NMI_B") (pin "1") (pinfunction "S_1") (pintype "passive"))
      (node (ref "QG2") (pin "7") (pinfunction "GND_7") (pintype "power_in"))
      (node (ref "S1") (pin "1") (pinfunction "S_1") (pintype "passive"))
      (node (ref "S1") (pin "2") (pinfunction "S1_2") (pintype "passive"))
      (node (ref "ST2") (pin "B1") (pinfunction "P_B1") (pintype "bidirectional"))
      (node (ref "ST2") (pin "B31") (pinfunction "P_B31") (pintype "bidirectional"))
      (node (ref "U$1") (pin "14") (pinfunction "GND_14") (pintype "bidirectional"))
      (node (ref "U$2") (pin "12") (pinfunction "GND_12") (pintype "bidirectional"))
      (node (ref "U$4") (pin "1") (pinfunction "GND_1") (pintype "power_in"))
      (node (ref "U$4") (pin "16") (pinfunction "DCD_16") (pintype "input"))
      (node (ref "U$4") (pin "17") (pinfunction "DSR_17") (pintype "input"))
      (node (ref "U$4") (pin "9") (pinfunction "CTS_9") (pintype "input"))
      (node (ref "U1") (pin "21") (pinfunction "VSS_21") (pintype "power_in"))
    )
    (net (code "67") (name "Net-(IC11A-1D)") (class "Default")
      (node (ref "IC11") (pin "2") (pinfunction "1D_2") (pintype "input"))
      (node (ref "IC11") (pin "6") (pinfunction "5D_6") (pintype "input"))
      (node (ref "IC11") (pin "7") (pinfunction "6D_7") (pintype "input"))
      (node (ref "IC11") (pin "8") (pinfunction "7D_8") (pintype "input"))
      (node (ref "IC11") (pin "9") (pinfunction "8D_9") (pintype "input"))
    )
    (net (code "68") (name "Net-(IO_LED-PadA)") (class "Default")
      (node (ref "IO_LED") (pin "A") (pinfunction "A_A") (pintype "passive"))
      (node (ref "R7") (pin "1") (pinfunction "1_1") (pintype "passive"))
    )
    (net (code "69") (name "Net-(IRQ_LED-PadA)") (class "Default")
      (node (ref "IRQ_LED") (pin "A") (pinfunction "A_A") (pintype "passive"))
      (node (ref "R6") (pin "1") (pinfunction "1_1") (pintype "passive"))
    )
    (net (code "70") (name "Net-(R5-Pad1)") (class "Default")
      (node (ref "R5") (pin "1") (pinfunction "1_1") (pintype "passive"))
      (node (ref "RESET") (pin "A") (pinfunction "A_A") (pintype "passive"))
    )
    (net (code "71") (name "Net-(U$4-XTL1)") (class "Default")
      (node (ref "C4") (pin "2") (pinfunction "2_2") (pintype "passive"))
      (node (ref "Q1") (pin "1") (pinfunction "1_1") (pintype "passive"))
      (node (ref "U$4") (pin "6") (pinfunction "XTL1_6") (pintype "input"))
    )
    (net (code "72") (name "Net-(U$4-XTL2)") (class "Default")
      (node (ref "Q1") (pin "2") (pinfunction "2_2") (pintype "passive"))
      (node (ref "U$4") (pin "7") (pinfunction "XTL2_7") (pintype "output"))
    )
    (net (code "73") (name "unconnected-(IC10A-EO-Pad15)") (class "Default")
      (node (ref "IC10") (pin "15") (pinfunction "EO_15") (pintype "output"))
    )
    (net (code "74") (name "unconnected-(IRQ1_B-P1-Pad4)") (class "Default")
      (node (ref "IRQ1_B") (pin "4") (pinfunction "P1_4") (pintype "passive"))
    )
    (net (code "75") (name "unconnected-(IRQ1_B-S1-Pad2)") (class "Default")
      (node (ref "IRQ1_B") (pin "2") (pinfunction "S1_2") (pintype "passive"))
    )
    (net (code "76") (name "unconnected-(JP3-Pad5)") (class "Default")
      (node (ref "JP3") (pin "5") (pinfunction "5_5") (pintype "passive"))
    )
    (net (code "77") (name "unconnected-(NMI_B-P1-Pad4)") (class "Default")
      (node (ref "NMI_B") (pin "4") (pinfunction "P1_4") (pintype "passive"))
    )
    (net (code "78") (name "unconnected-(NMI_B-S1-Pad2)") (class "Default")
      (node (ref "NMI_B") (pin "2") (pinfunction "S1_2") (pintype "passive"))
    )
    (net (code "79") (name "unconnected-(QG2-TS-Pad1)") (class "Default")
      (node (ref "QG2") (pin "1") (pinfunction "TS_1") (pintype "passive"))
    )
    (net (code "80") (name "unconnected-(ST2A-P-PadB9)") (class "Default")
      (node (ref "ST2") (pin "B9") (pinfunction "P_B9") (pintype "bidirectional"))
    )
    (net (code "81") (name "unconnected-(ST2AA-P-PadB16)") (class "Default")
      (node (ref "ST2") (pin "B16") (pinfunction "P_B16") (pintype "bidirectional"))
    )
    (net (code "82") (name "unconnected-(ST2AB-P-PadB17)") (class "Default")
      (node (ref "ST2") (pin "B17") (pinfunction "P_B17") (pintype "bidirectional"))
    )
    (net (code "83") (name "unconnected-(ST2AC-P-PadB18)") (class "Default")
      (node (ref "ST2") (pin "B18") (pinfunction "P_B18") (pintype "bidirectional"))
    )
    (net (code "84") (name "unconnected-(ST2AD-P-PadB26)") (class "Default")
      (node (ref "ST2") (pin "B26") (pinfunction "P_B26") (pintype "bidirectional"))
    )
    (net (code "85") (name "unconnected-(ST2AE-P-PadB27)") (class "Default")
      (node (ref "ST2") (pin "B27") (pinfunction "P_B27") (pintype "bidirectional"))
    )
    (net (code "86") (name "unconnected-(ST2AF-P-PadB28)") (class "Default")
      (node (ref "ST2") (pin "B28") (pinfunction "P_B28") (pintype "bidirectional"))
    )
    (net (code "87") (name "unconnected-(ST2AG-P-PadB4)") (class "Default")
      (node (ref "ST2") (pin "B4") (pinfunction "P_B4") (pintype "bidirectional"))
    )
    (net (code "88") (name "unconnected-(ST2AH-P-PadB5)") (class "Default")
      (node (ref "ST2") (pin "B5") (pinfunction "P_B5") (pintype "bidirectional"))
    )
    (net (code "89") (name "unconnected-(ST2AI-P-PadB6)") (class "Default")
      (node (ref "ST2") (pin "B6") (pinfunction "P_B6") (pintype "bidirectional"))
    )
    (net (code "90") (name "unconnected-(ST2AJ-P-PadB8)") (class "Default")
      (node (ref "ST2") (pin "B8") (pinfunction "P_B8") (pintype "bidirectional"))
    )
    (net (code "91") (name "unconnected-(ST2M-P-PadA15)") (class "Default")
      (node (ref "ST2") (pin "A15") (pinfunction "P_A15") (pintype "bidirectional"))
    )
    (net (code "92") (name "unconnected-(ST2N-P-PadA14)") (class "Default")
      (node (ref "ST2") (pin "A14") (pinfunction "P_A14") (pintype "bidirectional"))
    )
    (net (code "93") (name "unconnected-(ST2O-P-PadA13)") (class "Default")
      (node (ref "ST2") (pin "A13") (pinfunction "P_A13") (pintype "bidirectional"))
    )
    (net (code "94") (name "unconnected-(ST2P-P-PadA12)") (class "Default")
      (node (ref "ST2") (pin "A12") (pinfunction "P_A12") (pintype "bidirectional"))
    )
    (net (code "95") (name "unconnected-(ST2Y-P-PadB10)") (class "Default")
      (node (ref "ST2") (pin "B10") (pinfunction "P_B10") (pintype "bidirectional"))
    )
    (net (code "96") (name "unconnected-(ST2Z-P-PadB15)") (class "Default")
      (node (ref "ST2") (pin "B15") (pinfunction "P_B15") (pintype "bidirectional"))
    )
    (net (code "97") (name "unconnected-(U$2-IN10-Pad11)") (class "Default")
      (node (ref "U$2") (pin "11") (pinfunction "IN10_11") (pintype "bidirectional"))
    )
    (net (code "98") (name "unconnected-(U$2-IN11-Pad13)") (class "Default")
      (node (ref "U$2") (pin "13") (pinfunction "IN11_13") (pintype "bidirectional"))
    )
    (net (code "99") (name "unconnected-(U$4-DTR-Pad11)") (class "Default")
      (node (ref "U$4") (pin "11") (pinfunction "DTR_11") (pintype "output"))
    )
    (net (code "100") (name "unconnected-(U$4-RTS-Pad8)") (class "Default")
      (node (ref "U$4") (pin "8") (pinfunction "RTS_8") (pintype "output"))
    )
    (net (code "101") (name "unconnected-(U$4-RXC-Pad5)") (class "Default")
      (node (ref "U$4") (pin "5") (pinfunction "RXC_5") (pintype "bidirectional"))
    )
    (net (code "102") (name "unconnected-(U1-NC-Pad35)") (class "Default")
      (node (ref "U1") (pin "35") (pinfunction "NC_35") (pintype "no_connect"))
    )
    (net (code "103") (name "unconnected-(U1-PHI1-Pad3)") (class "Default")
      (node (ref "U1") (pin "3") (pinfunction "PHI1_3") (pintype "output"))
    )
    (net (code "104") (name "unconnected-(U1-SOB-Pad38)") (class "Default")
      (node (ref "U1") (pin "38") (pinfunction "SOB_38") (pintype "input"))
    )
  )
)
